# Recovery.net
KiCad netlist of a schematic drawn in Altium Designer
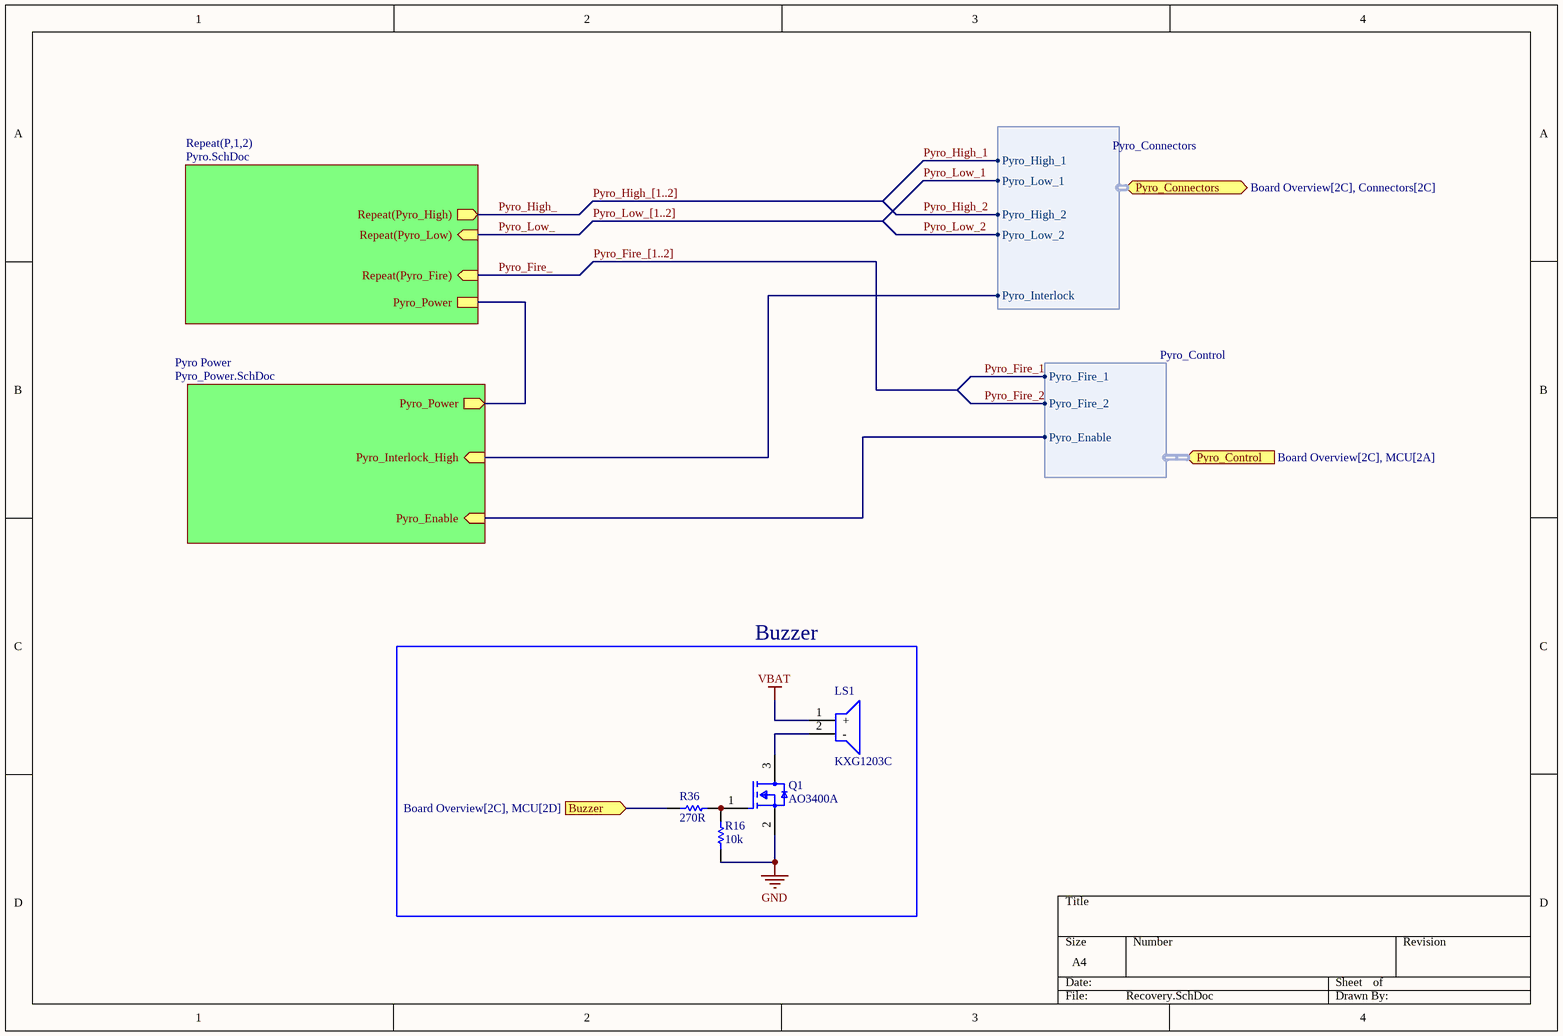
[diagram p0: Recovery.SchDoc]

(export (version "E")
  (design (tool "Eeschema 10.0.6"))
  (components
    (comp (ref "LS1")
      (value "KXG1203C")
      (footprint "KXG1203C")
      (description "Kingstate 5V dc PCB Mount Electromagnetic Buzzer")
      (fields (field (name "RS PART NUMBER") "7716957P"))
      (libsource (lib "StrathSEDS") (part "KXG1203C"))
    )
    (comp (ref "Q1")
      (value "AO3400A")
      (footprint "FP-SOT23-IPC_C")
      (description "N沟道 VDS=30V VGS=±12V ID=5.7A P=1.4W")
      (fields (field (name "LCSC PART #") "C20917"))
      (libsource (lib "StrathSEDS") (part "0a9ea7c96deaaede766a5b531c28de0"))
    )
    (comp (ref "R16")
      (value "10k")
      (footprint "RESC1609X50X30ML8T20")
      (description "Generic 0603 Resistor")
      (fields (field (name "TOLERANCE") "0%") (field (name "LCSC PART #") "C25804"))
      (libsource (lib "StrathSEDS") (part "RES-2"))
    )
    (comp (ref "R36")
      (value "270R")
      (footprint "RESC1609X50X30ML8T20")
      (description "Generic 0603 Resistor")
      (fields (field (name "TOLERANCE") "0%") (field (name "LCSC PART #") "C22966"))
      (libsource (lib "StrathSEDS") (part "RES-2"))
    )
  )
  (nets
    (net (code "3") (name "/Buzzer") (class "Default")
      (node (ref "R36") (pin "1") (pinfunction "1_1") (pintype "passive"))
    )
    (net (code "21") (name "GND") (class "Default")
      (node (ref "Q1") (pin "2") (pinfunction "S_2") (pintype "passive"))
      (node (ref "R16") (pin "1") (pinfunction "1_1") (pintype "passive"))
    )
    (net (code "22") (name "Net-(LS1--)") (class "Default")
      (node (ref "LS1") (pin "2") (pinfunction "-_2") (pintype "passive"))
      (node (ref "Q1") (pin "3") (pinfunction "D_3") (pintype "passive"))
    )
    (net (code "23") (name "Net-(Q1-G)") (class "Default")
      (node (ref "Q1") (pin "1") (pinfunction "G_1") (pintype "passive"))
      (node (ref "R16") (pin "2") (pinfunction "2_2") (pintype "passive"))
      (node (ref "R36") (pin "2") (pinfunction "2_2") (pintype "passive"))
    )
    (net (code "24") (name "VBAT") (class "Default")
      (node (ref "LS1") (pin "1") (pinfunction "+_1") (pintype "passive"))
    )
  )
)
